# mtorshield.net
KiCad netlist of a schematic drawn in EAGLE
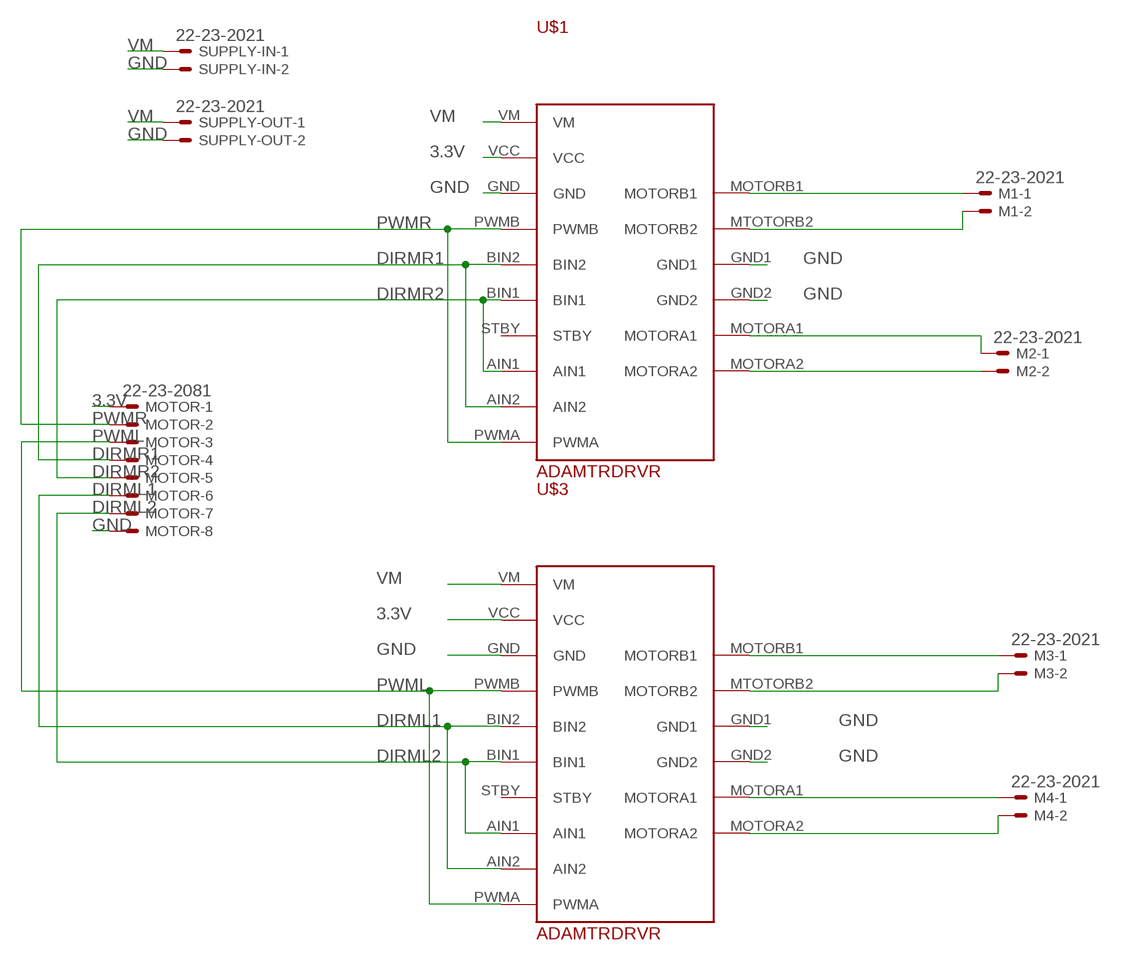
[diagram p0: schematic, sheet 1]

(export (version "E")
  (design (tool "Eeschema 10.0.6"))
  (components
    (comp (ref "M1")
      (value "22-23-2021")
      (footprint "eagle-import:22-23-2021")
      (fields (field (name "MF") "MOLEX"))
      (libsource (lib "eagle-import") (part "22-23-2021"))
    )
    (comp (ref "M2")
      (value "22-23-2021")
      (footprint "eagle-import:22-23-2021")
      (fields (field (name "MF") "MOLEX"))
      (libsource (lib "eagle-import") (part "22-23-2021"))
    )
    (comp (ref "M3")
      (value "22-23-2021")
      (footprint "eagle-import:22-23-2021")
      (fields (field (name "MF") "MOLEX"))
      (libsource (lib "eagle-import") (part "22-23-2021"))
    )
    (comp (ref "M4")
      (value "22-23-2021")
      (footprint "eagle-import:22-23-2021")
      (fields (field (name "MF") "MOLEX"))
      (libsource (lib "eagle-import") (part "22-23-2021"))
    )
    (comp (ref "MOTOR")
      (value "22-23-2081")
      (footprint "eagle-import:22-23-2081")
      (fields (field (name "MF") "MOLEX"))
      (libsource (lib "eagle-import") (part "22-23-2081"))
    )
    (comp (ref "SUPPLY-IN")
      (value "22-23-2021")
      (footprint "eagle-import:22-23-2021")
      (fields (field (name "MF") "MOLEX"))
      (libsource (lib "eagle-import") (part "22-23-2021"))
    )
    (comp (ref "SUPPLY-OUT")
      (value "22-23-2021")
      (footprint "eagle-import:22-23-2021")
      (fields (field (name "MF") "MOLEX"))
      (libsource (lib "eagle-import") (part "22-23-2021"))
    )
    (comp (ref "U$1")
      (value "ADAMTRDRVR")
      (footprint "eagle-import:ADAMTRDRVR")
      (libsource (lib "eagle-import") (part "ADAMTRDRVR"))
    )
    (comp (ref "U$3")
      (value "ADAMTRDRVR")
      (footprint "eagle-import:ADAMTRDRVR")
      (libsource (lib "eagle-import") (part "ADAMTRDRVR"))
    )
  )
  (nets
    (net (code "1") (name "/3.3V") (class "Default")
      (node (ref "MOTOR") (pin "1") (pinfunction "S_1") (pintype "passive"))
      (node (ref "U$1") (pin "VCC") (pinfunction "VCC_VCC") (pintype "bidirectional"))
      (node (ref "U$3") (pin "VCC") (pinfunction "VCC_VCC") (pintype "bidirectional"))
    )
    (net (code "2") (name "/DIRML1") (class "Default")
      (node (ref "MOTOR") (pin "6") (pinfunction "S_6") (pintype "passive"))
      (node (ref "U$3") (pin "AIN2") (pinfunction "AIN2_AIN2") (pintype "bidirectional"))
      (node (ref "U$3") (pin "BIN2") (pinfunction "BIN2_BIN2") (pintype "bidirectional"))
    )
    (net (code "3") (name "/DIRML2") (class "Default")
      (node (ref "MOTOR") (pin "7") (pinfunction "S_7") (pintype "passive"))
      (node (ref "U$3") (pin "AIN1") (pinfunction "AIN1_AIN1") (pintype "bidirectional"))
      (node (ref "U$3") (pin "BIN1") (pinfunction "BIN1_BIN1") (pintype "bidirectional"))
    )
    (net (code "4") (name "/DIRMR1") (class "Default")
      (node (ref "MOTOR") (pin "4") (pinfunction "S_4") (pintype "passive"))
      (node (ref "U$1") (pin "AIN2") (pinfunction "AIN2_AIN2") (pintype "bidirectional"))
      (node (ref "U$1") (pin "BIN2") (pinfunction "BIN2_BIN2") (pintype "bidirectional"))
    )
    (net (code "5") (name "/DIRMR2") (class "Default")
      (node (ref "MOTOR") (pin "5") (pinfunction "S_5") (pintype "passive"))
      (node (ref "U$1") (pin "AIN1") (pinfunction "AIN1_AIN1") (pintype "bidirectional"))
      (node (ref "U$1") (pin "BIN1") (pinfunction "BIN1_BIN1") (pintype "bidirectional"))
    )
    (net (code "6") (name "/GND") (class "Default")
      (node (ref "MOTOR") (pin "8") (pinfunction "S_8") (pintype "passive"))
      (node (ref "SUPPLY-IN") (pin "2") (pinfunction "S_2") (pintype "passive"))
      (node (ref "SUPPLY-OUT") (pin "2") (pinfunction "S_2") (pintype "passive"))
      (node (ref "U$1") (pin "GND") (pinfunction "GND_GND") (pintype "bidirectional"))
      (node (ref "U$1") (pin "GND1") (pinfunction "GND1_GND1") (pintype "bidirectional"))
      (node (ref "U$1") (pin "GND2") (pinfunction "GND2_GND2") (pintype "bidirectional"))
      (node (ref "U$3") (pin "GND") (pinfunction "GND_GND") (pintype "bidirectional"))
      (node (ref "U$3") (pin "GND1") (pinfunction "GND1_GND1") (pintype "bidirectional"))
      (node (ref "U$3") (pin "GND2") (pinfunction "GND2_GND2") (pintype "bidirectional"))
    )
    (net (code "7") (name "/PWML") (class "Default")
      (node (ref "MOTOR") (pin "3") (pinfunction "S_3") (pintype "passive"))
      (node (ref "U$3") (pin "PWMA") (pinfunction "PWMA_PWMA") (pintype "bidirectional"))
      (node (ref "U$3") (pin "PWMB") (pinfunction "PWMB_PWMB") (pintype "bidirectional"))
    )
    (net (code "8") (name "/PWMR") (class "Default")
      (node (ref "MOTOR") (pin "2") (pinfunction "S_2") (pintype "passive"))
      (node (ref "U$1") (pin "PWMA") (pinfunction "PWMA_PWMA") (pintype "bidirectional"))
      (node (ref "U$1") (pin "PWMB") (pinfunction "PWMB_PWMB") (pintype "bidirectional"))
    )
    (net (code "9") (name "/VM") (class "Default")
      (node (ref "SUPPLY-IN") (pin "1") (pinfunction "S_1") (pintype "passive"))
      (node (ref "SUPPLY-OUT") (pin "1") (pinfunction "S_1") (pintype "passive"))
      (node (ref "U$1") (pin "VM") (pinfunction "VM_VM") (pintype "bidirectional"))
      (node (ref "U$3") (pin "VM") (pinfunction "VM_VM") (pintype "bidirectional"))
    )
    (net (code "10") (name "Net-(M1A-S)") (class "Default")
      (node (ref "M1") (pin "1") (pinfunction "S_1") (pintype "passive"))
      (node (ref "U$1") (pin "MOTORB1") (pinfunction "MOTORB1_MOTORB1") (pintype "bidirectional"))
    )
    (net (code "11") (name "Net-(M1B-S)") (class "Default")
      (node (ref "M1") (pin "2") (pinfunction "S_2") (pintype "passive"))
      (node (ref "U$1") (pin "MTOTORB2") (pinfunction "MOTORB2_MTOTORB2") (pintype "bidirectional"))
    )
    (net (code "12") (name "Net-(M2A-S)") (class "Default")
      (node (ref "M2") (pin "1") (pinfunction "S_1") (pintype "passive"))
      (node (ref "U$1") (pin "MOTORA1") (pinfunction "MOTORA1_MOTORA1") (pintype "bidirectional"))
    )
    (net (code "13") (name "Net-(M2B-S)") (class "Default")
      (node (ref "M2") (pin "2") (pinfunction "S_2") (pintype "passive"))
      (node (ref "U$1") (pin "MOTORA2") (pinfunction "MOTORA2_MOTORA2") (pintype "bidirectional"))
    )
    (net (code "14") (name "Net-(M3A-S)") (class "Default")
      (node (ref "M3") (pin "1") (pinfunction "S_1") (pintype "passive"))
      (node (ref "U$3") (pin "MOTORB1") (pinfunction "MOTORB1_MOTORB1") (pintype "bidirectional"))
    )
    (net (code "15") (name "Net-(M3B-S)") (class "Default")
      (node (ref "M3") (pin "2") (pinfunction "S_2") (pintype "passive"))
      (node (ref "U$3") (pin "MTOTORB2") (pinfunction "MOTORB2_MTOTORB2") (pintype "bidirectional"))
    )
    (net (code "16") (name "Net-(M4A-S)") (class "Default")
      (node (ref "M4") (pin "1") (pinfunction "S_1") (pintype "passive"))
      (node (ref "U$3") (pin "MOTORA1") (pinfunction "MOTORA1_MOTORA1") (pintype "bidirectional"))
    )
    (net (code "17") (name "Net-(M4B-S)") (class "Default")
      (node (ref "M4") (pin "2") (pinfunction "S_2") (pintype "passive"))
      (node (ref "U$3") (pin "MOTORA2") (pinfunction "MOTORA2_MOTORA2") (pintype "bidirectional"))
    )
    (net (code "18") (name "unconnected-(U$1-PadSTBY)") (class "Default")
      (node (ref "U$1") (pin "STBY") (pinfunction "STBY_STBY") (pintype "bidirectional"))
    )
    (net (code "19") (name "unconnected-(U$3-PadSTBY)") (class "Default")
      (node (ref "U$3") (pin "STBY") (pinfunction "STBY_STBY") (pintype "bidirectional"))
    )
  )
)
